# VER2_0.net
KiCad netlist of a schematic drawn in EAGLE
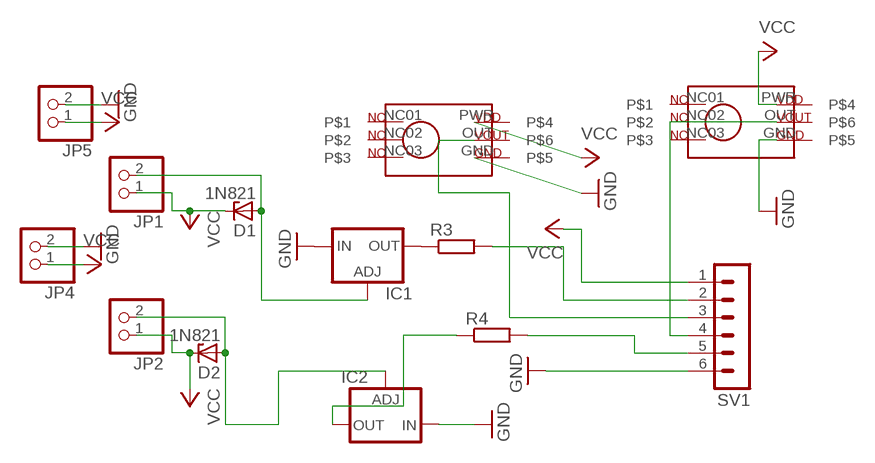
[diagram p0: schematic, sheet 1]

(export (version "E")
  (design (tool "Eeschema 10.0.6"))
  (components
    (comp (ref "D1")
      (value "1N821")
      (footprint "eagle-import:DO35Z10")
      (libsource (lib "eagle-import") (part "1N821"))
    )
    (comp (ref "D2")
      (value "1N821")
      (footprint "eagle-import:DO35Z10")
      (libsource (lib "eagle-import") (part "1N821"))
    )
    (comp (ref "IC1")
      (value "LM317TS")
      (footprint "eagle-import:317TS")
      (libsource (lib "eagle-import") (part "LM317TS"))
    )
    (comp (ref "IC2")
      (value "LM317TS")
      (footprint "eagle-import:317TS")
      (libsource (lib "eagle-import") (part "LM317TS"))
    )
    (comp (ref "JP1")
      (value "PINHD-1X2")
      (footprint "eagle-import:1X02")
      (libsource (lib "eagle-import") (part "PINHD-1X2"))
    )
    (comp (ref "JP2")
      (value "PINHD-1X2")
      (footprint "eagle-import:1X02")
      (libsource (lib "eagle-import") (part "PINHD-1X2"))
    )
    (comp (ref "JP4")
      (value "PINHD-1X2")
      (footprint "eagle-import:1X02")
      (libsource (lib "eagle-import") (part "PINHD-1X2"))
    )
    (comp (ref "JP5")
      (value "PINHD-1X2")
      (footprint "eagle-import:1X02")
      (libsource (lib "eagle-import") (part "PINHD-1X2"))
    )
    (comp (ref "R3")
      (value "R-EU_0207/10")
      (footprint "eagle-import:0207_10")
      (libsource (lib "eagle-import") (part "R-EU_0207/10"))
    )
    (comp (ref "R4")
      (value "R-EU_0207/10")
      (footprint "eagle-import:0207_10")
      (libsource (lib "eagle-import") (part "R-EU_0207/10"))
    )
    (comp (ref "SV1")
      (value "MA06-1")
      (footprint "eagle-import:MA06-1")
      (libsource (lib "eagle-import") (part "MA06-1"))
    )
    (comp (ref "U$1")
      (value "MIS-2500")
      (footprint "eagle-import:MIS-2500")
      (libsource (lib "eagle-import") (part "MIS-2500"))
    )
    (comp (ref "U$2")
      (value "MIS-2500")
      (footprint "eagle-import:MIS-2500")
      (libsource (lib "eagle-import") (part "MIS-2500"))
    )
  )
  (nets
    (net (code "1") (name "GND") (class "Default")
      (node (ref "IC1") (pin "3") (pinfunction "IN_3") (pintype "input"))
      (node (ref "IC2") (pin "3") (pinfunction "IN_3") (pintype "input"))
      (node (ref "JP4") (pin "2") (pinfunction "2_2") (pintype "passive"))
      (node (ref "JP5") (pin "2") (pinfunction "2_2") (pintype "passive"))
      (node (ref "SV1") (pin "6") (pinfunction "6_6") (pintype "passive"))
      (node (ref "U$1") (pin "GND") (pinfunction "P$5_GND") (pintype "power_in"))
      (node (ref "U$2") (pin "GND") (pinfunction "P$5_GND") (pintype "power_in"))
    )
    (net (code "2") (name "Net-(IC1-ADJ)") (class "Default")
      (node (ref "D1") (pin "A") (pinfunction "A_A") (pintype "passive"))
      (node (ref "IC1") (pin "1") (pinfunction "ADJ_1") (pintype "input"))
      (node (ref "JP1") (pin "2") (pinfunction "2_2") (pintype "passive"))
    )
    (net (code "3") (name "Net-(IC1-OUT)") (class "Default")
      (node (ref "IC1") (pin "2") (pinfunction "OUT_2") (pintype "passive"))
      (node (ref "R3") (pin "1") (pinfunction "1_1") (pintype "passive"))
    )
    (net (code "4") (name "Net-(IC2-ADJ)") (class "Default")
      (node (ref "D2") (pin "A") (pinfunction "A_A") (pintype "passive"))
      (node (ref "IC2") (pin "1") (pinfunction "ADJ_1") (pintype "input"))
      (node (ref "JP2") (pin "2") (pinfunction "2_2") (pintype "passive"))
    )
    (net (code "5") (name "Net-(IC2-OUT)") (class "Default")
      (node (ref "IC2") (pin "2") (pinfunction "OUT_2") (pintype "passive"))
      (node (ref "R4") (pin "1") (pinfunction "1_1") (pintype "passive"))
    )
    (net (code "6") (name "Net-(R3-Pad2)") (class "Default")
      (node (ref "R3") (pin "2") (pinfunction "2_2") (pintype "passive"))
      (node (ref "SV1") (pin "2") (pinfunction "2_2") (pintype "passive"))
    )
    (net (code "7") (name "Net-(R4-Pad2)") (class "Default")
      (node (ref "R4") (pin "2") (pinfunction "2_2") (pintype "passive"))
      (node (ref "SV1") (pin "5") (pinfunction "5_5") (pintype "passive"))
    )
    (net (code "8") (name "Net-(U$1-P$6)") (class "Default")
      (node (ref "SV1") (pin "3") (pinfunction "3_3") (pintype "passive"))
      (node (ref "U$1") (pin "OUT") (pinfunction "P$6_OUT") (pintype "output"))
    )
    (net (code "9") (name "Net-(U$2-P$6)") (class "Default")
      (node (ref "SV1") (pin "4") (pinfunction "4_4") (pintype "passive"))
      (node (ref "U$2") (pin "OUT") (pinfunction "P$6_OUT") (pintype "output"))
    )
    (net (code "10") (name "VCC") (class "Default")
      (node (ref "D1") (pin "C") (pinfunction "C_C") (pintype "passive"))
      (node (ref "D2") (pin "C") (pinfunction "C_C") (pintype "passive"))
      (node (ref "JP1") (pin "1") (pinfunction "1_1") (pintype "passive"))
      (node (ref "JP2") (pin "1") (pinfunction "1_1") (pintype "passive"))
      (node (ref "JP4") (pin "1") (pinfunction "1_1") (pintype "passive"))
      (node (ref "JP5") (pin "1") (pinfunction "1_1") (pintype "passive"))
      (node (ref "SV1") (pin "1") (pinfunction "1_1") (pintype "passive"))
      (node (ref "U$1") (pin "PWR") (pinfunction "P$4_PWR") (pintype "power_in"))
      (node (ref "U$2") (pin "PWR") (pinfunction "P$4_PWR") (pintype "power_in"))
    )
    (net (code "11") (name "unconnected-(U$1-P$1-PadNC01)") (class "Default")
      (node (ref "U$1") (pin "NC01") (pinfunction "P$1_NC01") (pintype "no_connect"))
    )
    (net (code "12") (name "unconnected-(U$1-P$2-PadNC02)") (class "Default")
      (node (ref "U$1") (pin "NC02") (pinfunction "P$2_NC02") (pintype "no_connect"))
    )
    (net (code "13") (name "unconnected-(U$1-P$3-PadNC03)") (class "Default")
      (node (ref "U$1") (pin "NC03") (pinfunction "P$3_NC03") (pintype "no_connect"))
    )
    (net (code "14") (name "unconnected-(U$2-P$1-PadNC01)") (class "Default")
      (node (ref "U$2") (pin "NC01") (pinfunction "P$1_NC01") (pintype "no_connect"))
    )
    (net (code "15") (name "unconnected-(U$2-P$2-PadNC02)") (class "Default")
      (node (ref "U$2") (pin "NC02") (pinfunction "P$2_NC02") (pintype "no_connect"))
    )
    (net (code "16") (name "unconnected-(U$2-P$3-PadNC03)") (class "Default")
      (node (ref "U$2") (pin "NC03") (pinfunction "P$3_NC03") (pintype "no_connect"))
    )
  )
)
